# ProtoShieldShort.net
KiCad netlist of a schematic drawn in EAGLE
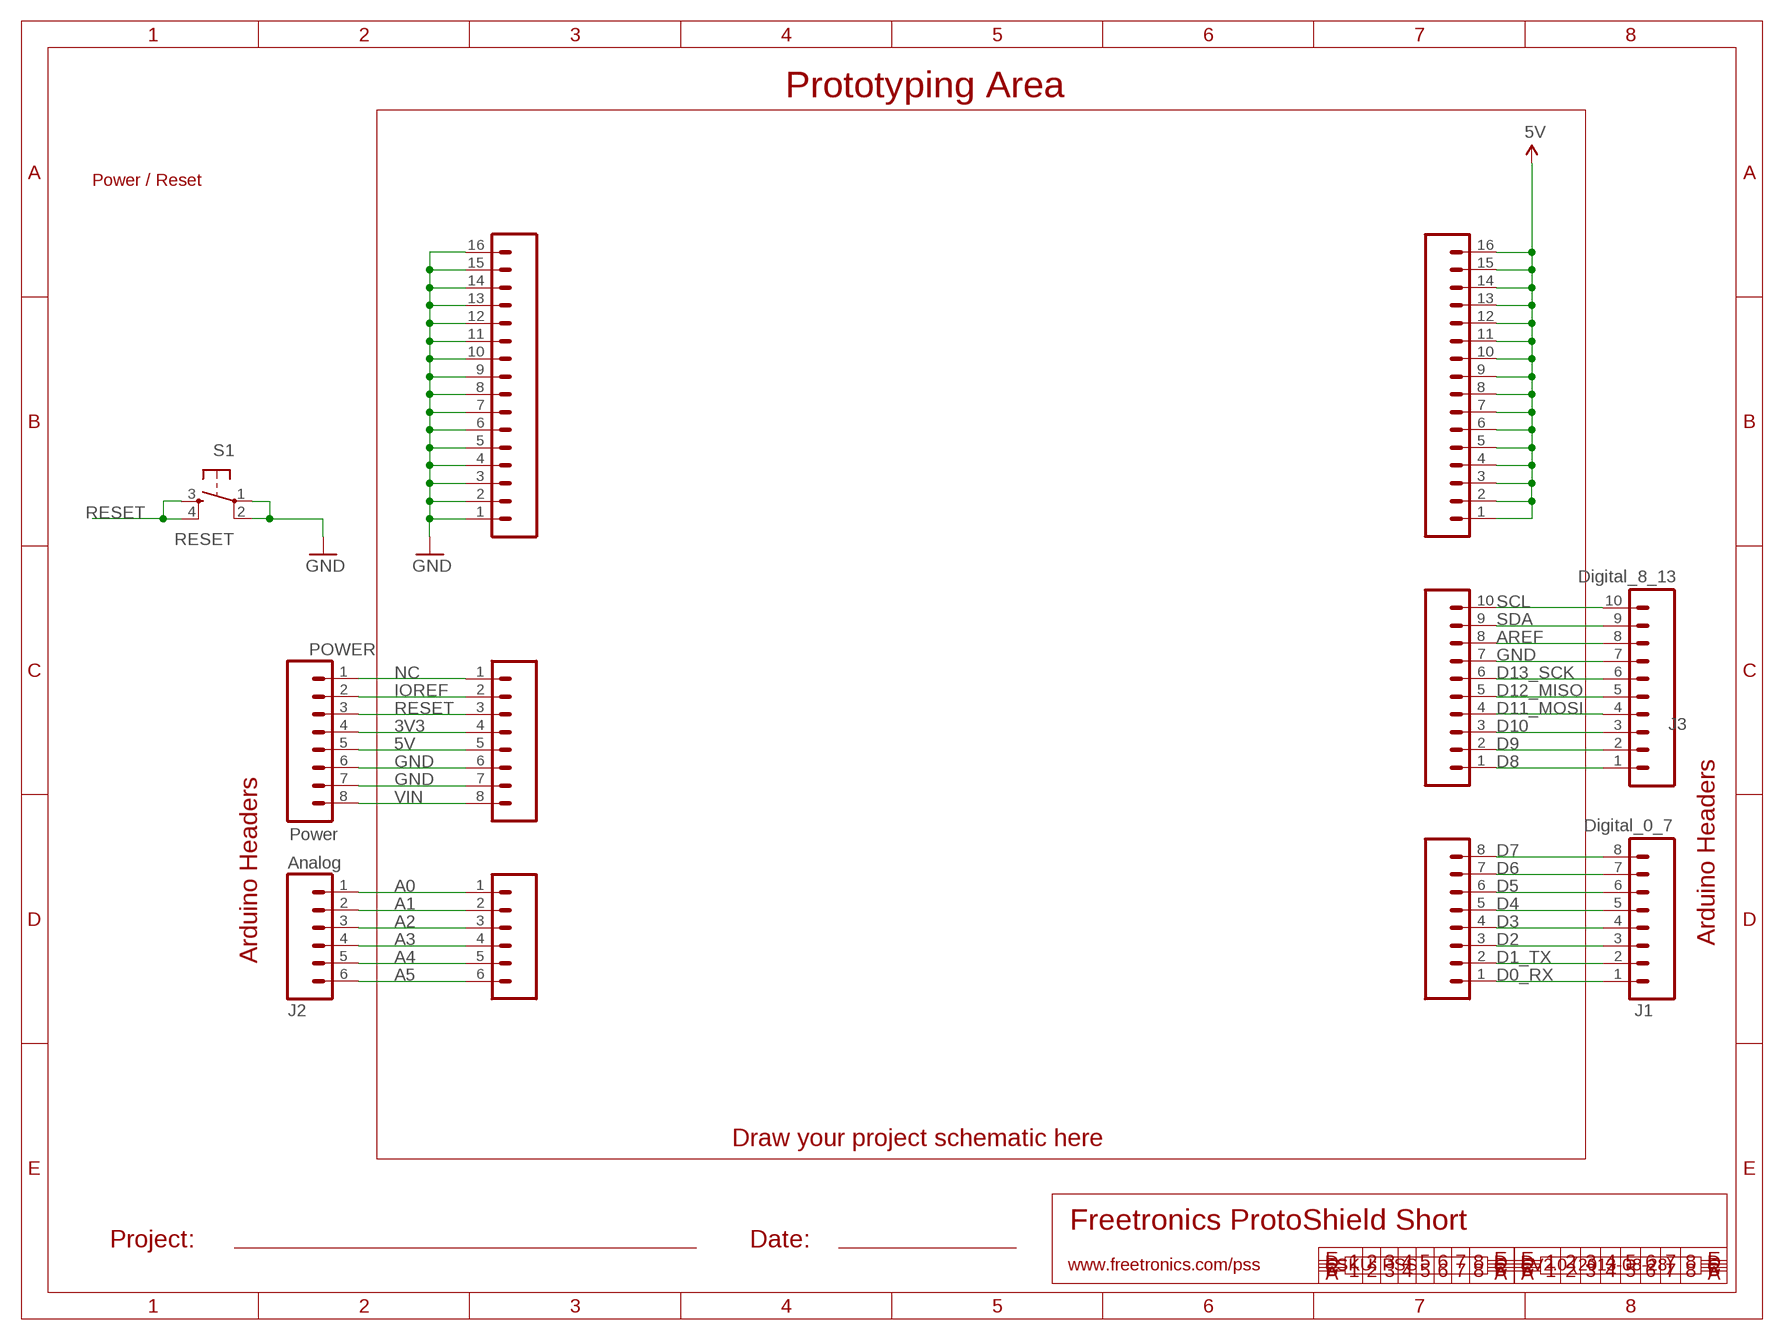
[diagram p0: schematic, sheet 1]

(export (version "E")
  (design (tool "Eeschema 10.0.6"))
  (components
    (comp (ref "J1")
      (value "Digital_0_7")
      (footprint "eagle-import:1X08")
      (libsource (lib "eagle-import") (part "M08"))
    )
    (comp (ref "J2")
      (value "Analog")
      (footprint "eagle-import:1X06")
      (libsource (lib "eagle-import") (part "M06SIP"))
    )
    (comp (ref "J3")
      (value "Digital_8_13")
      (footprint "eagle-import:1X10")
      (libsource (lib "eagle-import") (part "M100.1"))
    )
    (comp (ref "PADS_5V")
      (value "M16PTH")
      (footprint "eagle-import:1X16")
      (libsource (lib "eagle-import") (part "M16PTH"))
    )
    (comp (ref "PADS_GND")
      (value "M16PTH")
      (footprint "eagle-import:1X16")
      (libsource (lib "eagle-import") (part "M16PTH"))
    )
    (comp (ref "POWER")
      (value "Power")
      (footprint "eagle-import:1X08")
      (libsource (lib "eagle-import") (part "M08"))
    )
    (comp (ref "S1")
      (value "RESET")
      (footprint "eagle-import:TACTILE-PTH")
      (libsource (lib "eagle-import") (part "TAC_SWITCHPTH"))
    )
    (comp (ref "SL1")
      (value "Digital_0_7")
      (footprint "eagle-import:1X08")
      (libsource (lib "eagle-import") (part "M08"))
    )
    (comp (ref "SL2")
      (value "Analog")
      (footprint "eagle-import:1X06")
      (libsource (lib "eagle-import") (part "M06SIP"))
    )
    (comp (ref "SL3")
      (value "Digital_8_13")
      (footprint "eagle-import:1X10")
      (libsource (lib "eagle-import") (part "M100.1"))
    )
    (comp (ref "SLP")
      (value "Power")
      (footprint "eagle-import:1X08")
      (libsource (lib "eagle-import") (part "M08"))
    )
  )
  (nets
    (net (code "1") (name "/3V3") (class "Default")
      (node (ref "POWER") (pin "4") (pinfunction "4_4") (pintype "passive"))
      (node (ref "SLP") (pin "4") (pinfunction "4_4") (pintype "passive"))
    )
    (net (code "2") (name "/A0") (class "Default")
      (node (ref "J2") (pin "1") (pinfunction "1_1") (pintype "passive"))
      (node (ref "SL2") (pin "1") (pinfunction "1_1") (pintype "passive"))
    )
    (net (code "3") (name "/A1") (class "Default")
      (node (ref "J2") (pin "2") (pinfunction "2_2") (pintype "passive"))
      (node (ref "SL2") (pin "2") (pinfunction "2_2") (pintype "passive"))
    )
    (net (code "4") (name "/A2") (class "Default")
      (node (ref "J2") (pin "3") (pinfunction "3_3") (pintype "passive"))
      (node (ref "SL2") (pin "3") (pinfunction "3_3") (pintype "passive"))
    )
    (net (code "5") (name "/A3") (class "Default")
      (node (ref "J2") (pin "4") (pinfunction "4_4") (pintype "passive"))
      (node (ref "SL2") (pin "4") (pinfunction "4_4") (pintype "passive"))
    )
    (net (code "6") (name "/A4") (class "Default")
      (node (ref "J2") (pin "5") (pinfunction "5_5") (pintype "passive"))
      (node (ref "SL2") (pin "5") (pinfunction "5_5") (pintype "passive"))
    )
    (net (code "7") (name "/A5") (class "Default")
      (node (ref "J2") (pin "6") (pinfunction "6_6") (pintype "passive"))
      (node (ref "SL2") (pin "6") (pinfunction "6_6") (pintype "passive"))
    )
    (net (code "8") (name "/AREF") (class "Default")
      (node (ref "J3") (pin "8") (pinfunction "8_8") (pintype "passive"))
      (node (ref "SL3") (pin "8") (pinfunction "8_8") (pintype "passive"))
    )
    (net (code "9") (name "/D0_RX") (class "Default")
      (node (ref "J1") (pin "1") (pinfunction "1_1") (pintype "passive"))
      (node (ref "SL1") (pin "1") (pinfunction "1_1") (pintype "passive"))
    )
    (net (code "10") (name "/D1_TX") (class "Default")
      (node (ref "J1") (pin "2") (pinfunction "2_2") (pintype "passive"))
      (node (ref "SL1") (pin "2") (pinfunction "2_2") (pintype "passive"))
    )
    (net (code "11") (name "/D2") (class "Default")
      (node (ref "J1") (pin "3") (pinfunction "3_3") (pintype "passive"))
      (node (ref "SL1") (pin "3") (pinfunction "3_3") (pintype "passive"))
    )
    (net (code "12") (name "/D3") (class "Default")
      (node (ref "J1") (pin "4") (pinfunction "4_4") (pintype "passive"))
      (node (ref "SL1") (pin "4") (pinfunction "4_4") (pintype "passive"))
    )
    (net (code "13") (name "/D4") (class "Default")
      (node (ref "J1") (pin "5") (pinfunction "5_5") (pintype "passive"))
      (node (ref "SL1") (pin "5") (pinfunction "5_5") (pintype "passive"))
    )
    (net (code "14") (name "/D5") (class "Default")
      (node (ref "J1") (pin "6") (pinfunction "6_6") (pintype "passive"))
      (node (ref "SL1") (pin "6") (pinfunction "6_6") (pintype "passive"))
    )
    (net (code "15") (name "/D6") (class "Default")
      (node (ref "J1") (pin "7") (pinfunction "7_7") (pintype "passive"))
      (node (ref "SL1") (pin "7") (pinfunction "7_7") (pintype "passive"))
    )
    (net (code "16") (name "/D7") (class "Default")
      (node (ref "J1") (pin "8") (pinfunction "8_8") (pintype "passive"))
      (node (ref "SL1") (pin "8") (pinfunction "8_8") (pintype "passive"))
    )
    (net (code "17") (name "/D8") (class "Default")
      (node (ref "J3") (pin "1") (pinfunction "1_1") (pintype "passive"))
      (node (ref "SL3") (pin "1") (pinfunction "1_1") (pintype "passive"))
    )
    (net (code "18") (name "/D9") (class "Default")
      (node (ref "J3") (pin "2") (pinfunction "2_2") (pintype "passive"))
      (node (ref "SL3") (pin "2") (pinfunction "2_2") (pintype "passive"))
    )
    (net (code "19") (name "/D10") (class "Default")
      (node (ref "J3") (pin "3") (pinfunction "3_3") (pintype "passive"))
      (node (ref "SL3") (pin "3") (pinfunction "3_3") (pintype "passive"))
    )
    (net (code "20") (name "/D11_MOSI") (class "Default")
      (node (ref "J3") (pin "4") (pinfunction "4_4") (pintype "passive"))
      (node (ref "SL3") (pin "4") (pinfunction "4_4") (pintype "passive"))
    )
    (net (code "21") (name "/D12_MISO") (class "Default")
      (node (ref "J3") (pin "5") (pinfunction "5_5") (pintype "passive"))
      (node (ref "SL3") (pin "5") (pinfunction "5_5") (pintype "passive"))
    )
    (net (code "22") (name "/D13_SCK") (class "Default")
      (node (ref "J3") (pin "6") (pinfunction "6_6") (pintype "passive"))
      (node (ref "SL3") (pin "6") (pinfunction "6_6") (pintype "passive"))
    )
    (net (code "23") (name "/IOREF") (class "Default")
      (node (ref "POWER") (pin "2") (pinfunction "2_2") (pintype "passive"))
      (node (ref "SLP") (pin "2") (pinfunction "2_2") (pintype "passive"))
    )
    (net (code "24") (name "/NC") (class "Default")
      (node (ref "POWER") (pin "1") (pinfunction "1_1") (pintype "passive"))
      (node (ref "SLP") (pin "1") (pinfunction "1_1") (pintype "passive"))
    )
    (net (code "25") (name "/RESET") (class "Default")
      (node (ref "POWER") (pin "3") (pinfunction "3_3") (pintype "passive"))
      (node (ref "S1") (pin "3") (pinfunction "3_3") (pintype "passive"))
      (node (ref "S1") (pin "4") (pinfunction "4_4") (pintype "passive"))
      (node (ref "SLP") (pin "3") (pinfunction "3_3") (pintype "passive"))
    )
    (net (code "26") (name "/SCL") (class "Default")
      (node (ref "J3") (pin "10") (pinfunction "10_10") (pintype "passive"))
      (node (ref "SL3") (pin "10") (pinfunction "10_10") (pintype "passive"))
    )
    (net (code "27") (name "/SDA") (class "Default")
      (node (ref "J3") (pin "9") (pinfunction "9_9") (pintype "passive"))
      (node (ref "SL3") (pin "9") (pinfunction "9_9") (pintype "passive"))
    )
    (net (code "28") (name "/VIN") (class "Default")
      (node (ref "POWER") (pin "8") (pinfunction "8_8") (pintype "passive"))
      (node (ref "SLP") (pin "8") (pinfunction "8_8") (pintype "passive"))
    )
    (net (code "29") (name "5V") (class "Default")
      (node (ref "PADS_5V") (pin "1") (pinfunction "1_1") (pintype "passive"))
      (node (ref "PADS_5V") (pin "10") (pinfunction "10_10") (pintype "passive"))
      (node (ref "PADS_5V") (pin "11") (pinfunction "11_11") (pintype "passive"))
      (node (ref "PADS_5V") (pin "12") (pinfunction "12_12") (pintype "passive"))
      (node (ref "PADS_5V") (pin "13") (pinfunction "13_13") (pintype "passive"))
      (node (ref "PADS_5V") (pin "14") (pinfunction "14_14") (pintype "passive"))
      (node (ref "PADS_5V") (pin "15") (pinfunction "15_15") (pintype "passive"))
      (node (ref "PADS_5V") (pin "16") (pinfunction "16_16") (pintype "passive"))
      (node (ref "PADS_5V") (pin "2") (pinfunction "2_2") (pintype "passive"))
      (node (ref "PADS_5V") (pin "3") (pinfunction "3_3") (pintype "passive"))
      (node (ref "PADS_5V") (pin "4") (pinfunction "4_4") (pintype "passive"))
      (node (ref "PADS_5V") (pin "5") (pinfunction "5_5") (pintype "passive"))
      (node (ref "PADS_5V") (pin "6") (pinfunction "6_6") (pintype "passive"))
      (node (ref "PADS_5V") (pin "7") (pinfunction "7_7") (pintype "passive"))
      (node (ref "PADS_5V") (pin "8") (pinfunction "8_8") (pintype "passive"))
      (node (ref "PADS_5V") (pin "9") (pinfunction "9_9") (pintype "passive"))
      (node (ref "POWER") (pin "5") (pinfunction "5_5") (pintype "passive"))
      (node (ref "SLP") (pin "5") (pinfunction "5_5") (pintype "passive"))
    )
    (net (code "30") (name "GND") (class "Default")
      (node (ref "J3") (pin "7") (pinfunction "7_7") (pintype "passive"))
      (node (ref "PADS_GND") (pin "1") (pinfunction "1_1") (pintype "passive"))
      (node (ref "PADS_GND") (pin "10") (pinfunction "10_10") (pintype "passive"))
      (node (ref "PADS_GND") (pin "11") (pinfunction "11_11") (pintype "passive"))
      (node (ref "PADS_GND") (pin "12") (pinfunction "12_12") (pintype "passive"))
      (node (ref "PADS_GND") (pin "13") (pinfunction "13_13") (pintype "passive"))
      (node (ref "PADS_GND") (pin "14") (pinfunction "14_14") (pintype "passive"))
      (node (ref "PADS_GND") (pin "15") (pinfunction "15_15") (pintype "passive"))
      (node (ref "PADS_GND") (pin "16") (pinfunction "16_16") (pintype "passive"))
      (node (ref "PADS_GND") (pin "2") (pinfunction "2_2") (pintype "passive"))
      (node (ref "PADS_GND") (pin "3") (pinfunction "3_3") (pintype "passive"))
      (node (ref "PADS_GND") (pin "4") (pinfunction "4_4") (pintype "passive"))
      (node (ref "PADS_GND") (pin "5") (pinfunction "5_5") (pintype "passive"))
      (node (ref "PADS_GND") (pin "6") (pinfunction "6_6") (pintype "passive"))
      (node (ref "PADS_GND") (pin "7") (pinfunction "7_7") (pintype "passive"))
      (node (ref "PADS_GND") (pin "8") (pinfunction "8_8") (pintype "passive"))
      (node (ref "PADS_GND") (pin "9") (pinfunction "9_9") (pintype "passive"))
      (node (ref "POWER") (pin "6") (pinfunction "6_6") (pintype "passive"))
      (node (ref "POWER") (pin "7") (pinfunction "7_7") (pintype "passive"))
      (node (ref "S1") (pin "1") (pinfunction "1_1") (pintype "passive"))
      (node (ref "S1") (pin "2") (pinfunction "2_2") (pintype "passive"))
      (node (ref "SL3") (pin "7") (pinfunction "7_7") (pintype "passive"))
      (node (ref "SLP") (pin "6") (pinfunction "6_6") (pintype "passive"))
      (node (ref "SLP") (pin "7") (pinfunction "7_7") (pintype "passive"))
    )
  )
)
